# design.net
KiCad netlist of a schematic drawn in Altium Designer
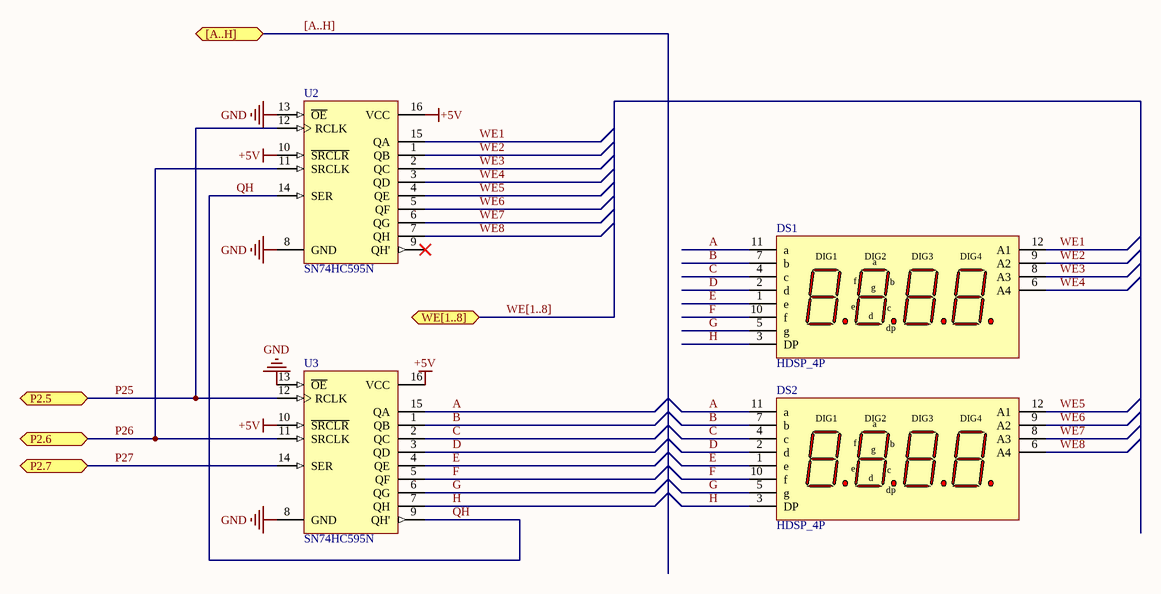
[diagram p0: 数码管.SchDoc]

(export (version "E")
  (design (tool "Eeschema 10.0.6"))
  (components
    (comp (ref "DS1")
      (value "HDSP_4P")
      (footprint "51开发板封装库_W:HDSP_B4_数码管")
      (libsource (lib "Schlib1") (part "HDSP_4P"))
    )
    (comp (ref "DS2")
      (value "HDSP_4P")
      (footprint "51开发板封装库_W:HDSP_B4_数码管")
      (libsource (lib "Schlib1") (part "HDSP_4P"))
    )
    (comp (ref "U2")
      (value "SN74HC595N")
      (footprint "N016")
      (description "8-Bit Shift Register with 3-State Output Registers")
      (fields (field (name "PUBLISHER") "Altium Limited"))
      (libsource (lib "TI Logic Register") (part "SN74HC595N"))
    )
    (comp (ref "U3")
      (value "SN74HC595N")
      (footprint "N016")
      (description "8-Bit Shift Register with 3-State Output Registers")
      (fields (field (name "PUBLISHER") "Altium Limited"))
      (libsource (lib "TI Logic Register") (part "SN74HC595N"))
    )
  )
  (nets
    (net (code "2") (name "+5V") (class "Default")
      (node (ref "U2") (pin "10") (pinfunction "~{SRCLR}_10") (pintype "input"))
      (node (ref "U2") (pin "16") (pinfunction "VCC_16") (pintype "power_in"))
      (node (ref "U3") (pin "10") (pinfunction "~{SRCLR}_10") (pintype "input"))
      (node (ref "U3") (pin "16") (pinfunction "VCC_16") (pintype "power_in"))
    )
    (net (code "3") (name "/A") (class "Default")
      (node (ref "DS1") (pin "11") (pinfunction "a_11") (pintype "passive"))
      (node (ref "DS2") (pin "11") (pinfunction "a_11") (pintype "passive"))
      (node (ref "U3") (pin "15") (pinfunction "QA_15") (pintype "tri_state"))
    )
    (net (code "4") (name "/B") (class "Default")
      (node (ref "DS1") (pin "7") (pinfunction "b_7") (pintype "passive"))
      (node (ref "DS2") (pin "7") (pinfunction "b_7") (pintype "passive"))
      (node (ref "U3") (pin "1") (pinfunction "QB_1") (pintype "tri_state"))
    )
    (net (code "5") (name "/C") (class "Default")
      (node (ref "DS1") (pin "4") (pinfunction "c_4") (pintype "passive"))
      (node (ref "DS2") (pin "4") (pinfunction "c_4") (pintype "passive"))
      (node (ref "U3") (pin "2") (pinfunction "QC_2") (pintype "tri_state"))
    )
    (net (code "6") (name "/D") (class "Default")
      (node (ref "DS1") (pin "2") (pinfunction "d_2") (pintype "passive"))
      (node (ref "DS2") (pin "2") (pinfunction "d_2") (pintype "passive"))
      (node (ref "U3") (pin "3") (pinfunction "QD_3") (pintype "tri_state"))
    )
    (net (code "7") (name "/E") (class "Default")
      (node (ref "DS1") (pin "1") (pinfunction "e_1") (pintype "passive"))
      (node (ref "DS2") (pin "1") (pinfunction "e_1") (pintype "passive"))
      (node (ref "U3") (pin "4") (pinfunction "QE_4") (pintype "tri_state"))
    )
    (net (code "8") (name "/F") (class "Default")
      (node (ref "DS1") (pin "10") (pinfunction "f_10") (pintype "passive"))
      (node (ref "DS2") (pin "10") (pinfunction "f_10") (pintype "passive"))
      (node (ref "U3") (pin "5") (pinfunction "QF_5") (pintype "tri_state"))
    )
    (net (code "9") (name "/G") (class "Default")
      (node (ref "DS1") (pin "5") (pinfunction "g_5") (pintype "passive"))
      (node (ref "DS2") (pin "5") (pinfunction "g_5") (pintype "passive"))
      (node (ref "U3") (pin "6") (pinfunction "QG_6") (pintype "tri_state"))
    )
    (net (code "10") (name "/H") (class "Default")
      (node (ref "DS1") (pin "3") (pinfunction "DP_3") (pintype "passive"))
      (node (ref "DS2") (pin "3") (pinfunction "DP_3") (pintype "passive"))
      (node (ref "U3") (pin "7") (pinfunction "QH_7") (pintype "tri_state"))
    )
    (net (code "11") (name "/P25") (class "Default")
      (node (ref "U2") (pin "12") (pinfunction "RCLK_12") (pintype "input"))
      (node (ref "U3") (pin "12") (pinfunction "RCLK_12") (pintype "input"))
    )
    (net (code "12") (name "/P26") (class "Default")
      (node (ref "U2") (pin "11") (pinfunction "SRCLK_11") (pintype "input"))
      (node (ref "U3") (pin "11") (pinfunction "SRCLK_11") (pintype "input"))
    )
    (net (code "13") (name "/P27") (class "Default")
      (node (ref "U3") (pin "14") (pinfunction "SER_14") (pintype "input"))
    )
    (net (code "14") (name "/QH") (class "Default")
      (node (ref "U2") (pin "14") (pinfunction "SER_14") (pintype "input"))
      (node (ref "U3") (pin "9") (pinfunction "QH'_9") (pintype "output"))
    )
    (net (code "15") (name "/WE1") (class "Default")
      (node (ref "DS1") (pin "12") (pinfunction "A1_12") (pintype "passive"))
      (node (ref "U2") (pin "15") (pinfunction "QA_15") (pintype "tri_state"))
    )
    (net (code "16") (name "/WE2") (class "Default")
      (node (ref "DS1") (pin "9") (pinfunction "A2_9") (pintype "passive"))
      (node (ref "U2") (pin "1") (pinfunction "QB_1") (pintype "tri_state"))
    )
    (net (code "17") (name "/WE3") (class "Default")
      (node (ref "DS1") (pin "8") (pinfunction "A3_8") (pintype "passive"))
      (node (ref "U2") (pin "2") (pinfunction "QC_2") (pintype "tri_state"))
    )
    (net (code "18") (name "/WE4") (class "Default")
      (node (ref "DS1") (pin "6") (pinfunction "A4_6") (pintype "passive"))
      (node (ref "U2") (pin "3") (pinfunction "QD_3") (pintype "tri_state"))
    )
    (net (code "19") (name "/WE5") (class "Default")
      (node (ref "DS2") (pin "12") (pinfunction "A1_12") (pintype "passive"))
      (node (ref "U2") (pin "4") (pinfunction "QE_4") (pintype "tri_state"))
    )
    (net (code "20") (name "/WE6") (class "Default")
      (node (ref "DS2") (pin "9") (pinfunction "A2_9") (pintype "passive"))
      (node (ref "U2") (pin "5") (pinfunction "QF_5") (pintype "tri_state"))
    )
    (net (code "21") (name "/WE7") (class "Default")
      (node (ref "DS2") (pin "8") (pinfunction "A3_8") (pintype "passive"))
      (node (ref "U2") (pin "6") (pinfunction "QG_6") (pintype "tri_state"))
    )
    (net (code "22") (name "/WE8") (class "Default")
      (node (ref "DS2") (pin "6") (pinfunction "A4_6") (pintype "passive"))
      (node (ref "U2") (pin "7") (pinfunction "QH_7") (pintype "tri_state"))
    )
    (net (code "25") (name "GND") (class "Default")
      (node (ref "U2") (pin "13") (pinfunction "~{OE}_13") (pintype "input"))
      (node (ref "U2") (pin "8") (pinfunction "GND_8") (pintype "power_in"))
      (node (ref "U3") (pin "13") (pinfunction "~{OE}_13") (pintype "input"))
      (node (ref "U3") (pin "8") (pinfunction "GND_8") (pintype "power_in"))
    )
    (net (code "26") (name "unconnected-(U2-QH'-Pad9)") (class "Default")
      (node (ref "U2") (pin "9") (pinfunction "QH'_9") (pintype "output+no_connect"))
    )
  )
)
